# UltraSoonSensor.net
KiCad netlist of a schematic drawn in Altium Designer
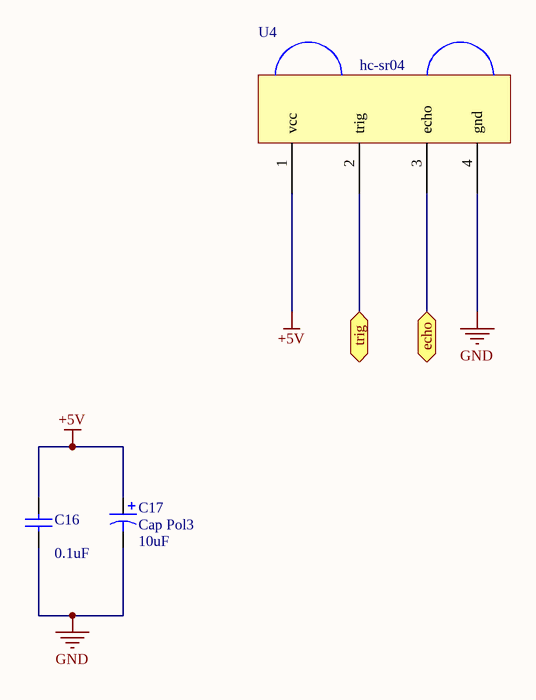
[diagram p0: UltraSoonSensor.SchDoc]

(export (version "E")
  (design (tool "Eeschema 10.0.6"))
  (components
    (comp (ref "C16")
      (value "0.1uF")
      (footprint "C1206")
      (description "Capacitor (Semiconductor SIM Model)")
      (fields (field (name "Comment") "Cap Semi") (field (name "PUBLISHER") "Altium Limited"))
      (libsource (lib "Miscellaneous Devices") (part "Cap Semi"))
    )
    (comp (ref "C17")
      (value "Cap Pol3")
      (footprint "C0805")
      (description "Polarized Capacitor (Surface Mount)")
      (fields (field (name "ALTIUM_VALUE") "10uF") (field (name "PUBLISHER") "Altium Limited"))
      (libsource (lib "Miscellaneous Devices") (part "Cap Pol3"))
    )
    (comp (ref "U4")
      (value "hc-sr04")
      (footprint "ultrasoonSensor")
      (libsource (lib "ultrasoon") (part "Component_1"))
    )
  )
  (nets
    (net (code "1") (name "+5V") (class "Default")
      (node (ref "C16") (pin "1") (pinfunction "1_1") (pintype "passive"))
      (node (ref "C17") (pin "1") (pinfunction "1_1") (pintype "passive"))
      (node (ref "U4") (pin "1") (pinfunction "vcc_1") (pintype "passive"))
    )
    (net (code "2") (name "/echo") (class "Default")
      (node (ref "U4") (pin "3") (pinfunction "echo_3") (pintype "passive"))
    )
    (net (code "3") (name "/trig") (class "Default")
      (node (ref "U4") (pin "2") (pinfunction "trig_2") (pintype "passive"))
    )
    (net (code "4") (name "GND") (class "Default")
      (node (ref "C16") (pin "2") (pinfunction "2_2") (pintype "passive"))
      (node (ref "C17") (pin "2") (pinfunction "2_2") (pintype "passive"))
      (node (ref "U4") (pin "4") (pinfunction "gnd_4") (pintype "passive"))
    )
  )
)
